# HeaterInterface.net
KiCad netlist of a schematic drawn in EAGLE
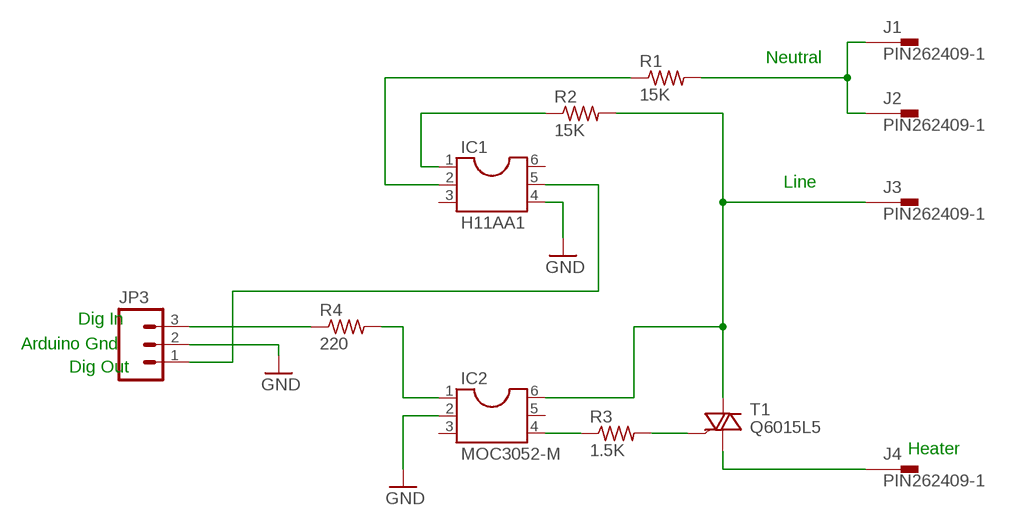
[diagram p0: schematic, sheet 1]

(export (version "E")
  (design (tool "Eeschema 10.0.6"))
  (components
    (comp (ref "IC1")
      (value "H11AA1")
      (footprint "eagle-import:DIL06")
      (libsource (lib "eagle-import") (part "DIL6"))
    )
    (comp (ref "IC2")
      (value "MOC3052-M")
      (footprint "eagle-import:DIL06")
      (libsource (lib "eagle-import") (part "DIL6"))
    )
    (comp (ref "J1")
      (value "PIN262409-1")
      (footprint "eagle-import:62409-1")
      (libsource (lib "eagle-import") (part "PIN262409-1"))
    )
    (comp (ref "J2")
      (value "PIN262409-1")
      (footprint "eagle-import:62409-1")
      (libsource (lib "eagle-import") (part "PIN262409-1"))
    )
    (comp (ref "J3")
      (value "PIN262409-1")
      (footprint "eagle-import:62409-1")
      (libsource (lib "eagle-import") (part "PIN262409-1"))
    )
    (comp (ref "J4")
      (value "PIN262409-1")
      (footprint "eagle-import:62409-1")
      (libsource (lib "eagle-import") (part "PIN262409-1"))
    )
    (comp (ref "JP3")
      (value "M03PTH")
      (footprint "eagle-import:1X03")
      (libsource (lib "eagle-import") (part "M03PTH"))
    )
    (comp (ref "R1")
      (value "15K")
      (footprint "eagle-import:0207_10")
      (libsource (lib "eagle-import") (part "R-US_0207/10"))
    )
    (comp (ref "R2")
      (value "15K")
      (footprint "eagle-import:0207_10")
      (libsource (lib "eagle-import") (part "R-US_0207/10"))
    )
    (comp (ref "R3")
      (value "1.5K")
      (footprint "eagle-import:0207_10")
      (libsource (lib "eagle-import") (part "R-US_0207/10"))
    )
    (comp (ref "R4")
      (value "220")
      (footprint "eagle-import:0207_10")
      (libsource (lib "eagle-import") (part "R-US_0207/10"))
    )
    (comp (ref "T1")
      (value "Q6015L5")
      (footprint "eagle-import:TO220BH")
      (libsource (lib "eagle-import") (part "BT138-H"))
    )
  )
  (nets
    (net (code "1") (name "GND") (class "Default")
      (node (ref "IC1") (pin "4") (pinfunction "4_4") (pintype "passive"))
      (node (ref "IC2") (pin "2") (pinfunction "2_2") (pintype "passive"))
      (node (ref "JP3") (pin "2") (pinfunction "2_2") (pintype "passive"))
    )
    (net (code "2") (name "Net-(IC1-Pad1)") (class "Default")
      (node (ref "IC1") (pin "1") (pinfunction "1_1") (pintype "passive"))
      (node (ref "R2") (pin "1") (pinfunction "1_1") (pintype "passive"))
    )
    (net (code "3") (name "Net-(IC1-Pad2)") (class "Default")
      (node (ref "IC1") (pin "2") (pinfunction "2_2") (pintype "passive"))
      (node (ref "R1") (pin "1") (pinfunction "1_1") (pintype "passive"))
    )
    (net (code "4") (name "Net-(IC1-Pad5)") (class "Default")
      (node (ref "IC1") (pin "5") (pinfunction "5_5") (pintype "passive"))
      (node (ref "JP3") (pin "1") (pinfunction "1_1") (pintype "passive"))
    )
    (net (code "5") (name "Net-(IC2-Pad1)") (class "Default")
      (node (ref "IC2") (pin "1") (pinfunction "1_1") (pintype "passive"))
      (node (ref "R4") (pin "2") (pinfunction "2_2") (pintype "passive"))
    )
    (net (code "6") (name "Net-(IC2-Pad4)") (class "Default")
      (node (ref "IC2") (pin "4") (pinfunction "4_4") (pintype "passive"))
      (node (ref "R3") (pin "1") (pinfunction "1_1") (pintype "passive"))
    )
    (net (code "7") (name "Net-(J1-1)") (class "Default")
      (node (ref "J1") (pin "A1") (pinfunction "1_A1") (pintype "passive"))
      (node (ref "J2") (pin "A1") (pinfunction "1_A1") (pintype "passive"))
      (node (ref "R1") (pin "2") (pinfunction "2_2") (pintype "passive"))
    )
    (net (code "8") (name "Net-(J3-1)") (class "Default")
      (node (ref "IC2") (pin "6") (pinfunction "6_6") (pintype "passive"))
      (node (ref "J3") (pin "A1") (pinfunction "1_A1") (pintype "passive"))
      (node (ref "R2") (pin "2") (pinfunction "2_2") (pintype "passive"))
      (node (ref "T1") (pin "T2") (pinfunction "A2_T2") (pintype "passive"))
    )
    (net (code "9") (name "Net-(J4-1)") (class "Default")
      (node (ref "J4") (pin "A1") (pinfunction "1_A1") (pintype "passive"))
      (node (ref "T1") (pin "T1") (pinfunction "A1_T1") (pintype "passive"))
    )
    (net (code "10") (name "Net-(JP3-Pad3)") (class "Default")
      (node (ref "JP3") (pin "3") (pinfunction "3_3") (pintype "passive"))
      (node (ref "R4") (pin "1") (pinfunction "1_1") (pintype "passive"))
    )
    (net (code "11") (name "Net-(R3-Pad2)") (class "Default")
      (node (ref "R3") (pin "2") (pinfunction "2_2") (pintype "passive"))
      (node (ref "T1") (pin "G") (pinfunction "G_G") (pintype "passive"))
    )
    (net (code "12") (name "unconnected-(IC1-Pad3)") (class "Default")
      (node (ref "IC1") (pin "3") (pinfunction "3_3") (pintype "passive"))
    )
    (net (code "13") (name "unconnected-(IC1-Pad6)") (class "Default")
      (node (ref "IC1") (pin "6") (pinfunction "6_6") (pintype "passive"))
    )
    (net (code "14") (name "unconnected-(IC2-Pad3)") (class "Default")
      (node (ref "IC2") (pin "3") (pinfunction "3_3") (pintype "passive"))
    )
    (net (code "15") (name "unconnected-(IC2-Pad5)") (class "Default")
      (node (ref "IC2") (pin "5") (pinfunction "5_5") (pintype "passive"))
    )
    (net (code "16") (name "unconnected-(J1-1.1-PadA2)") (class "Default")
      (node (ref "J1") (pin "A2") (pinfunction "1.1_A2") (pintype "passive"))
    )
    (net (code "17") (name "unconnected-(J2-1.1-PadA2)") (class "Default")
      (node (ref "J2") (pin "A2") (pinfunction "1.1_A2") (pintype "passive"))
    )
    (net (code "18") (name "unconnected-(J3-1.1-PadA2)") (class "Default")
      (node (ref "J3") (pin "A2") (pinfunction "1.1_A2") (pintype "passive"))
    )
    (net (code "19") (name "unconnected-(J4-1.1-PadA2)") (class "Default")
      (node (ref "J4") (pin "A2") (pinfunction "1.1_A2") (pintype "passive"))
    )
  )
)
